# Digital_Processing.net
KiCad netlist of a schematic drawn in Altium Designer
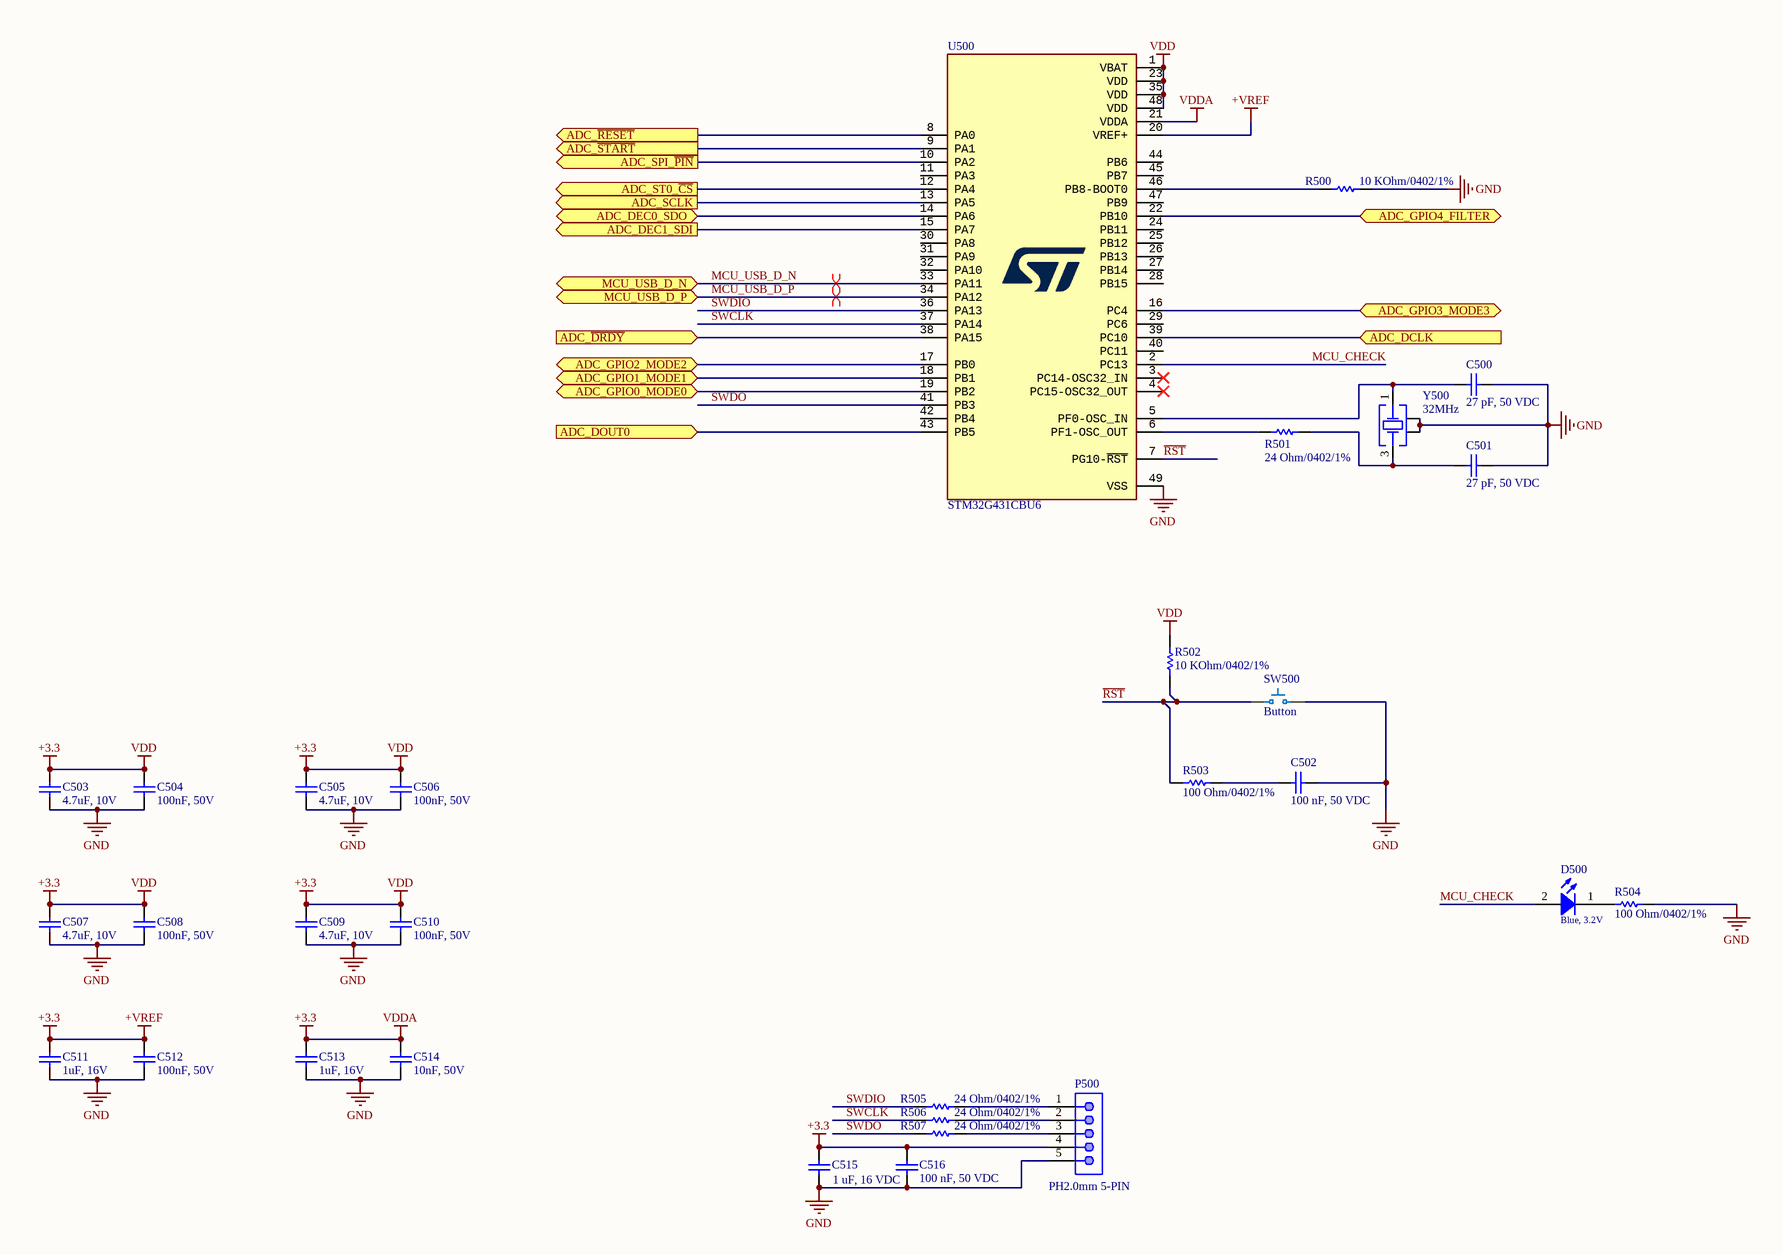
[diagram p0: Digital Processing.SchDoc]

(export (version "E")
  (design (tool "Eeschema 10.0.6"))
  (components
    (comp (ref "C500")
      (value "27 pF, 50 VDC")
      (footprint "CAP_0603")
      (description "CAP, size 0603, 22 pF, 50 VDC")
      (fields (field (name "TOLERANCE") "+/-5%"))
      (libsource (lib "Altium_Ceramic_Cap") (part "0106032200550"))
    )
    (comp (ref "C501")
      (value "27 pF, 50 VDC")
      (footprint "CAP_0603")
      (description "CAP, size 0603, 22 pF, 50 VDC")
      (fields (field (name "TOLERANCE") "+/-5%"))
      (libsource (lib "Altium_Ceramic_Cap") (part "0106032200550"))
    )
    (comp (ref "C502")
      (value "100 nF, 50 VDC")
      (footprint "CAP_0603")
      (description "CAP, size 0603, 100 nF, 50 VDC")
      (fields (field (name "TOLERANCE") "+/-10%"))
      (libsource (lib "Altium_Ceramic_Cap") (part "0106031041050"))
    )
    (comp (ref "C503")
      (value "4.7uF, 10V")
      (footprint "WCAP-CSGP_0402_L1W0.5H0.5")
      (description "WCAP-CSGP Multilayer Ceramic Chip Capacitor, General Purpose, size 0402, X5R, 4.7μF, 6.3V")
      (fields
        (field (name "MANUFACTURER PART NUMBER") "885012105008")
        (field (name "MANUFACTURER") "Wurth Elektronik")
      )
      (libsource (lib "Altium_WCAP-CSGP (rev24c)") (part "885012105008"))
    )
    (comp (ref "C504")
      (value "100nF, 50V")
      (footprint "WCAP-CSGP_0402_L1W0.5H0.5")
      (description "WCAP-CSGP Multilayer Ceramic Chip Capacitor, General Purpose, size 0402, X7R, 100nF, 50V")
      (fields
        (field (name "MANUFACTURER PART NUMBER") "885012205086")
        (field (name "MANUFACTURER") "Wurth Elektronik")
      )
      (libsource (lib "Altium_WCAP-CSGP (rev24c)") (part "885012205086"))
    )
    (comp (ref "C505")
      (value "4.7uF, 10V")
      (footprint "WCAP-CSGP_0402_L1W0.5H0.5")
      (description "WCAP-CSGP Multilayer Ceramic Chip Capacitor, General Purpose, size 0402, X5R, 4.7μF, 6.3V")
      (fields
        (field (name "MANUFACTURER PART NUMBER") "885012105008")
        (field (name "MANUFACTURER") "Wurth Elektronik")
      )
      (libsource (lib "Altium_WCAP-CSGP (rev24c)") (part "885012105008"))
    )
    (comp (ref "C506")
      (value "100nF, 50V")
      (footprint "WCAP-CSGP_0402_L1W0.5H0.5")
      (description "WCAP-CSGP Multilayer Ceramic Chip Capacitor, General Purpose, size 0402, X7R, 100nF, 50V")
      (fields
        (field (name "MANUFACTURER PART NUMBER") "885012205086")
        (field (name "MANUFACTURER") "Wurth Elektronik")
      )
      (libsource (lib "Altium_WCAP-CSGP (rev24c)") (part "885012205086"))
    )
    (comp (ref "C507")
      (value "4.7uF, 10V")
      (footprint "WCAP-CSGP_0402_L1W0.5H0.5")
      (description "WCAP-CSGP Multilayer Ceramic Chip Capacitor, General Purpose, size 0402, X5R, 4.7μF, 6.3V")
      (fields
        (field (name "MANUFACTURER PART NUMBER") "885012105008")
        (field (name "MANUFACTURER") "Wurth Elektronik")
      )
      (libsource (lib "Altium_WCAP-CSGP (rev24c)") (part "885012105008"))
    )
    (comp (ref "C508")
      (value "100nF, 50V")
      (footprint "WCAP-CSGP_0402_L1W0.5H0.5")
      (description "WCAP-CSGP Multilayer Ceramic Chip Capacitor, General Purpose, size 0402, X7R, 100nF, 50V")
      (fields
        (field (name "MANUFACTURER PART NUMBER") "885012205086")
        (field (name "MANUFACTURER") "Wurth Elektronik")
      )
      (libsource (lib "Altium_WCAP-CSGP (rev24c)") (part "885012205086"))
    )
    (comp (ref "C509")
      (value "4.7uF, 10V")
      (footprint "WCAP-CSGP_0402_L1W0.5H0.5")
      (description "WCAP-CSGP Multilayer Ceramic Chip Capacitor, General Purpose, size 0402, X5R, 4.7μF, 6.3V")
      (fields
        (field (name "MANUFACTURER PART NUMBER") "885012105008")
        (field (name "MANUFACTURER") "Wurth Elektronik")
      )
      (libsource (lib "Altium_WCAP-CSGP (rev24c)") (part "885012105008"))
    )
    (comp (ref "C510")
      (value "100nF, 50V")
      (footprint "WCAP-CSGP_0402_L1W0.5H0.5")
      (description "WCAP-CSGP Multilayer Ceramic Chip Capacitor, General Purpose, size 0402, X7R, 100nF, 50V")
      (fields
        (field (name "MANUFACTURER PART NUMBER") "885012205086")
        (field (name "MANUFACTURER") "Wurth Elektronik")
      )
      (libsource (lib "Altium_WCAP-CSGP (rev24c)") (part "885012205086"))
    )
    (comp (ref "C511")
      (value "1uF, 16V")
      (footprint "WCAP-CSGP_0402_L1W0.5H0.5")
      (description "1 µF ±10% 16V Ceramic Capacitor X7R 0603 (1608 Metric)")
      (fields
        (field (name "MANUFACTURER PART NUMBER") "885012105012")
        (field (name "MANUFACTURER") "Wurth Elektronik")
      )
      (libsource (lib "Altium_WCAP-CSGP (rev24c)") (part "885012105012"))
    )
    (comp (ref "C512")
      (value "100nF, 50V")
      (footprint "WCAP-CSGP_0402_L1W0.5H0.5")
      (description "WCAP-CSGP Multilayer Ceramic Chip Capacitor, General Purpose, size 0402, X7R, 100nF, 50V")
      (fields
        (field (name "MANUFACTURER PART NUMBER") "885012205086")
        (field (name "MANUFACTURER") "Wurth Elektronik")
      )
      (libsource (lib "Altium_WCAP-CSGP (rev24c)") (part "885012205086"))
    )
    (comp (ref "C513")
      (value "1uF, 16V")
      (footprint "WCAP-CSGP_0402_L1W0.5H0.5")
      (description "1 µF ±10% 16V Ceramic Capacitor X7R 0603 (1608 Metric)")
      (fields
        (field (name "MANUFACTURER PART NUMBER") "885012105012")
        (field (name "MANUFACTURER") "Wurth Elektronik")
      )
      (libsource (lib "Altium_WCAP-CSGP (rev24c)") (part "885012105012"))
    )
    (comp (ref "C514")
      (value "10nF, 50V")
      (footprint "WCAP-CSGP_0402_L1W0.5H0.5")
      (description "WCAP-CSGP Multilayer Ceramic Chip Capacitor, General Purpose, size 0402, X7R, 10nF, 50V")
      (fields
        (field (name "MANUFACTURER PART NUMBER") "885012205067")
        (field (name "MANUFACTURER") "Wurth Elektronik")
      )
      (libsource (lib "Altium_WCAP-CSGP (rev24c)") (part "885012205067"))
    )
    (comp (ref "C515")
      (value "1 uF, 16 VDC")
      (footprint "CAP_0603")
      (description "CAP, size 0603, 1 uF, 16 VDC")
      (fields (field (name "TOLERANCE") "+/-10%"))
      (libsource (lib "Altium_Ceramic_Cap") (part "0106031051016"))
    )
    (comp (ref "C516")
      (value "100 nF, 50 VDC")
      (footprint "CAP_0603")
      (description "CAP, size 0603, 100 nF, 50 VDC")
      (fields (field (name "TOLERANCE") "+/-10%"))
      (libsource (lib "Altium_Ceramic_Cap") (part "0106031041050"))
    )
    (comp (ref "D500")
      (value "Blue, 3.2V")
      (footprint "WL-SMCW_0805")
      (description "WL-SMCW SMT Mono-color Chip LED Waterclear, size 0805, Blue, 3.2V, 140deg")
      (libsource (lib "Altium_LED") (part "160805BlueClear"))
    )
    (comp (ref "P500")
      (value "PH2.0mm 5-PIN")
      (footprint "620105131822")
      (description "WR-WTB SMT Male Horizontal Shrouded Header, pitch 2mm, 5p")
      (fields (field (name "PART NUMBER") "620105131822") (field (name "MANUFACTURER") "Wurth Elektronik"))
      (libsource (lib "Altium_PCB_Connector") (part "620105131822"))
    )
    (comp (ref "R500")
      (value "10 KOhm/0402/1%")
      (footprint "R0402")
      (description "Code 103, 1/16W 1%")
      (fields (field (name "Comment") "Resistor 10 KOhm 0402 1%"))
      (libsource (lib "Giang_Resistor") (part "Resistor 10 KOhm 0402 1%"))
    )
    (comp (ref "R501")
      (value "24 Ohm/0402/1%")
      (footprint "R0402")
      (description "1/16W Thick Film Resistors 50V ±5% ±200ppm/℃ 24Ω 0402 Chip Resistor - Surface Mount ROHS")
      (fields (field (name "Comment") "Resistor 24 Ohm 0402 1%"))
      (libsource (lib "Giang_Resistor") (part "Resistor 24 Ohm 0402 1%"))
    )
    (comp (ref "R502")
      (value "10 KOhm/0402/1%")
      (footprint "R0402")
      (description "Code 103, 1/16W 1%")
      (fields (field (name "Comment") "Resistor 10 KOhm 0402 1%"))
      (libsource (lib "Giang_Resistor") (part "Resistor 10 KOhm 0402 1%"))
    )
    (comp (ref "R503")
      (value "100 Ohm/0402/1%")
      (footprint "R0402")
      (description "Code 104, 1/16W")
      (fields (field (name "Comment") "Resistor 100 Ohm 0402 1%"))
      (libsource (lib "Giang_Resistor") (part "Resistor 100 Ohm 0402 1%"))
    )
    (comp (ref "R504")
      (value "100 Ohm/0402/1%")
      (footprint "R0402")
      (description "Code 104, 1/16W")
      (fields (field (name "Comment") "Resistor 100 Ohm 0402 1%"))
      (libsource (lib "Giang_Resistor") (part "Resistor 100 Ohm 0402 1%"))
    )
    (comp (ref "R505")
      (value "24 Ohm/0402/1%")
      (footprint "R0402")
      (description "1/16W Thick Film Resistors 50V ±5% ±200ppm/℃ 24Ω 0402 Chip Resistor - Surface Mount ROHS")
      (fields (field (name "Comment") "Resistor 24 Ohm 0402 1%"))
      (libsource (lib "Giang_Resistor") (part "Resistor 24 Ohm 0402 1%"))
    )
    (comp (ref "R506")
      (value "24 Ohm/0402/1%")
      (footprint "R0402")
      (description "1/16W Thick Film Resistors 50V ±5% ±200ppm/℃ 24Ω 0402 Chip Resistor - Surface Mount ROHS")
      (fields (field (name "Comment") "Resistor 24 Ohm 0402 1%"))
      (libsource (lib "Giang_Resistor") (part "Resistor 24 Ohm 0402 1%"))
    )
    (comp (ref "R507")
      (value "24 Ohm/0402/1%")
      (footprint "R0402")
      (description "1/16W Thick Film Resistors 50V ±5% ±200ppm/℃ 24Ω 0402 Chip Resistor - Surface Mount ROHS")
      (fields (field (name "Comment") "Resistor 24 Ohm 0402 1%"))
      (libsource (lib "Giang_Resistor") (part "Resistor 24 Ohm 0402 1%"))
    )
    (comp (ref "SW500")
      (value "Button")
      (footprint "Button_3x4mm_SMD_2P")
      (fields (field (name "SUPPLY PART NUMBER") "Tụ Gốm 0603 20pF 50V"))
      (libsource (lib "BluetoothTracking") (part "Button_SMD_3x4mm_2P"))
    )
    (comp (ref "U500")
      (value "STM32G431CBU6")
      (footprint "QFN50P700X700X60-49N")
      (libsource (lib "Giang_MCU") (part "STM32G431CBU6"))
    )
    (comp (ref "Y500")
      (value "32MHz")
      (footprint "WE-XTAL_CFPX-104")
      (description "WE-XTAL Quartz Crystal, SMT, CFPX-104, 32MHz, +/-20ppm")
      (fields
        (field (name "MANUFACTURER PART NUMBER") "830059535")
        (field (name "MANUFACTURER") "Wurth Elektronik")
      )
      (libsource (lib "Altium_WE-XTAL (rev22a)") (part "830059535"))
    )
  )
  (nets
    (net (code "1") (name "+3.3") (class "Default")
      (node (ref "C503") (pin "2") (pinfunction "2_2") (pintype "passive"))
      (node (ref "C504") (pin "2") (pinfunction "2_2") (pintype "passive"))
      (node (ref "C505") (pin "2") (pinfunction "2_2") (pintype "passive"))
      (node (ref "C506") (pin "2") (pinfunction "2_2") (pintype "passive"))
      (node (ref "C507") (pin "2") (pinfunction "2_2") (pintype "passive"))
      (node (ref "C508") (pin "2") (pinfunction "2_2") (pintype "passive"))
      (node (ref "C509") (pin "2") (pinfunction "2_2") (pintype "passive"))
      (node (ref "C510") (pin "2") (pinfunction "2_2") (pintype "passive"))
      (node (ref "C511") (pin "1") (pinfunction "1_1") (pintype "passive"))
      (node (ref "C512") (pin "2") (pinfunction "2_2") (pintype "passive"))
      (node (ref "C513") (pin "1") (pinfunction "1_1") (pintype "passive"))
      (node (ref "C514") (pin "2") (pinfunction "2_2") (pintype "passive"))
      (node (ref "C515") (pin "2") (pinfunction "2_2") (pintype "passive"))
      (node (ref "C516") (pin "1") (pinfunction "1_1") (pintype "passive"))
      (node (ref "P500") (pin "4") (pinfunction "4_4") (pintype "passive"))
      (node (ref "R502") (pin "1") (pinfunction "1_1") (pintype "passive"))
      (node (ref "U500") (pin "1") (pinfunction "VBAT_1") (pintype "passive"))
      (node (ref "U500") (pin "20") (pinfunction "VREF+_20") (pintype "passive"))
      (node (ref "U500") (pin "21") (pinfunction "VDDA_21") (pintype "passive"))
      (node (ref "U500") (pin "23") (pinfunction "VDD_23") (pintype "passive"))
      (node (ref "U500") (pin "35") (pinfunction "VDD_35") (pintype "passive"))
      (node (ref "U500") (pin "48") (pinfunction "VDD_48") (pintype "passive"))
    )
    (net (code "2") (name "/ADC_DCLK") (class "Default")
      (node (ref "U500") (pin "39") (pinfunction "PC10_39") (pintype "passive"))
    )
    (net (code "3") (name "/ADC_DEC0_SDO") (class "Default")
      (node (ref "U500") (pin "14") (pinfunction "PA6_14") (pintype "passive"))
    )
    (net (code "4") (name "/ADC_DEC1_SDI") (class "Default")
      (node (ref "U500") (pin "15") (pinfunction "PA7_15") (pintype "passive"))
    )
    (net (code "5") (name "/ADC_DOUT0") (class "Default")
      (node (ref "U500") (pin "43") (pinfunction "PB5_43") (pintype "passive"))
    )
    (net (code "6") (name "/ADC_GPIO0_MODE0") (class "Default")
      (node (ref "U500") (pin "19") (pinfunction "PB2_19") (pintype "passive"))
    )
    (net (code "7") (name "/ADC_GPIO1_MODE1") (class "Default")
      (node (ref "U500") (pin "18") (pinfunction "PB1_18") (pintype "passive"))
    )
    (net (code "8") (name "/ADC_GPIO2_MODE2") (class "Default")
      (node (ref "U500") (pin "17") (pinfunction "PB0_17") (pintype "passive"))
    )
    (net (code "9") (name "/ADC_GPIO3_MODE3") (class "Default")
      (node (ref "U500") (pin "16") (pinfunction "PC4_16") (pintype "passive"))
    )
    (net (code "10") (name "/ADC_GPIO4_FILTER") (class "Default")
      (node (ref "U500") (pin "22") (pinfunction "PB10_22") (pintype "passive"))
    )
    (net (code "11") (name "/ADC_SCLK") (class "Default")
      (node (ref "U500") (pin "13") (pinfunction "PA5_13") (pintype "passive"))
    )
    (net (code "12") (name "/ADC_SPI_~{PIN}") (class "Default")
      (node (ref "U500") (pin "10") (pinfunction "PA2_10") (pintype "passive"))
    )
    (net (code "13") (name "/ADC_ST0_~{CS}") (class "Default")
      (node (ref "U500") (pin "12") (pinfunction "PA4_12") (pintype "passive"))
    )
    (net (code "14") (name "/ADC_~{DRDY}") (class "Default")
      (node (ref "U500") (pin "38") (pinfunction "PA15_38") (pintype "passive"))
    )
    (net (code "15") (name "/ADC_~{RESET}") (class "Default")
      (node (ref "U500") (pin "8") (pinfunction "PA0_8") (pintype "passive"))
    )
    (net (code "16") (name "/ADC_~{START}") (class "Default")
      (node (ref "U500") (pin "9") (pinfunction "PA1_9") (pintype "passive"))
    )
    (net (code "17") (name "/MCU_CHECK") (class "Default")
      (node (ref "D500") (pin "2") (pinfunction "A_2") (pintype "passive"))
      (node (ref "U500") (pin "2") (pinfunction "PC13_2") (pintype "passive"))
    )
    (net (code "18") (name "/MCU_USB_D_N") (class "Default")
      (node (ref "U500") (pin "33") (pinfunction "PA11_33") (pintype "passive"))
    )
    (net (code "19") (name "/MCU_USB_D_P") (class "Default")
      (node (ref "U500") (pin "34") (pinfunction "PA12_34") (pintype "passive"))
    )
    (net (code "20") (name "/SWCLK") (class "Default")
      (node (ref "R506") (pin "1") (pinfunction "1_1") (pintype "passive"))
      (node (ref "U500") (pin "37") (pinfunction "PA14_37") (pintype "passive"))
    )
    (net (code "21") (name "/SWDIO") (class "Default")
      (node (ref "R505") (pin "1") (pinfunction "1_1") (pintype "passive"))
      (node (ref "U500") (pin "36") (pinfunction "PA13_36") (pintype "passive"))
    )
    (net (code "22") (name "/SWDO") (class "Default")
      (node (ref "R507") (pin "1") (pinfunction "1_1") (pintype "passive"))
      (node (ref "U500") (pin "41") (pinfunction "PB3_41") (pintype "passive"))
    )
    (net (code "23") (name "/~{RST}") (class "Default")
      (node (ref "R502") (pin "2") (pinfunction "2_2") (pintype "passive"))
      (node (ref "R503") (pin "1") (pinfunction "1_1") (pintype "passive"))
      (node (ref "SW500") (pin "1") (pinfunction "1_1") (pintype "passive"))
      (node (ref "U500") (pin "7") (pinfunction "PG10-~{RST}_7") (pintype "passive"))
    )
    (net (code "24") (name "GND") (class "Default")
      (node (ref "C500") (pin "1") (pinfunction "1_1") (pintype "passive"))
      (node (ref "C501") (pin "1") (pinfunction "1_1") (pintype "passive"))
      (node (ref "C502") (pin "2") (pinfunction "2_2") (pintype "passive"))
      (node (ref "C503") (pin "1") (pinfunction "1_1") (pintype "passive"))
      (node (ref "C504") (pin "1") (pinfunction "1_1") (pintype "passive"))
      (node (ref "C505") (pin "1") (pinfunction "1_1") (pintype "passive"))
      (node (ref "C506") (pin "1") (pinfunction "1_1") (pintype "passive"))
      (node (ref "C507") (pin "1") (pinfunction "1_1") (pintype "passive"))
      (node (ref "C508") (pin "1") (pinfunction "1_1") (pintype "passive"))
      (node (ref "C509") (pin "1") (pinfunction "1_1") (pintype "passive"))
      (node (ref "C510") (pin "1") (pinfunction "1_1") (pintype "passive"))
      (node (ref "C511") (pin "2") (pinfunction "2_2") (pintype "passive"))
      (node (ref "C512") (pin "1") (pinfunction "1_1") (pintype "passive"))
      (node (ref "C513") (pin "2") (pinfunction "2_2") (pintype "passive"))
      (node (ref "C514") (pin "1") (pinfunction "1_1") (pintype "passive"))
      (node (ref "C515") (pin "1") (pinfunction "1_1") (pintype "passive"))
      (node (ref "C516") (pin "2") (pinfunction "2_2") (pintype "passive"))
      (node (ref "P500") (pin "5") (pinfunction "5_5") (pintype "passive"))
      (node (ref "R500") (pin "2") (pinfunction "2_2") (pintype "passive"))
      (node (ref "R504") (pin "2") (pinfunction "2_2") (pintype "passive"))
      (node (ref "SW500") (pin "2") (pinfunction "2_2") (pintype "passive"))
      (node (ref "U500") (pin "49") (pinfunction "VSS_49") (pintype "passive"))
      (node (ref "Y500") (pin "2") (pinfunction "GND_&_Lid_2") (pintype "passive"))
      (node (ref "Y500") (pin "4") (pinfunction "GND_&_Lid_4") (pintype "passive"))
    )
    (net (code "25") (name "Net-(C501-Pad2)") (class "Default")
      (node (ref "C501") (pin "2") (pinfunction "2_2") (pintype "passive"))
      (node (ref "R501") (pin "2") (pinfunction "2_2") (pintype "passive"))
      (node (ref "Y500") (pin "3") (pinfunction "Crystal_3") (pintype "passive"))
    )
    (net (code "26") (name "Net-(C502-Pad1)") (class "Default")
      (node (ref "C502") (pin "1") (pinfunction "1_1") (pintype "passive"))
      (node (ref "R503") (pin "2") (pinfunction "2_2") (pintype "passive"))
    )
    (net (code "27") (name "Net-(D500-K)") (class "Default")
      (node (ref "D500") (pin "1") (pinfunction "K_1") (pintype "passive"))
      (node (ref "R504") (pin "1") (pinfunction "1_1") (pintype "passive"))
    )
    (net (code "28") (name "Net-(P500-Pad1)") (class "Default")
      (node (ref "P500") (pin "1") (pinfunction "1_1") (pintype "passive"))
      (node (ref "R505") (pin "2") (pinfunction "2_2") (pintype "passive"))
    )
    (net (code "29") (name "Net-(P500-Pad2)") (class "Default")
      (node (ref "P500") (pin "2") (pinfunction "2_2") (pintype "passive"))
      (node (ref "R506") (pin "2") (pinfunction "2_2") (pintype "passive"))
    )
    (net (code "30") (name "Net-(P500-Pad3)") (class "Default")
      (node (ref "P500") (pin "3") (pinfunction "3_3") (pintype "passive"))
      (node (ref "R507") (pin "2") (pinfunction "2_2") (pintype "passive"))
    )
    (net (code "31") (name "Net-(U500-PB8-BOOT0)") (class "Default")
      (node (ref "R500") (pin "1") (pinfunction "1_1") (pintype "passive"))
      (node (ref "U500") (pin "46") (pinfunction "PB8-BOOT0_46") (pintype "passive"))
    )
    (net (code "32") (name "Net-(U500-PF0-OSC_IN)") (class "Default")
      (node (ref "C500") (pin "2") (pinfunction "2_2") (pintype "passive"))
      (node (ref "U500") (pin "5") (pinfunction "PF0-OSC_IN_5") (pintype "passive"))
      (node (ref "Y500") (pin "1") (pinfunction "Crystal_1") (pintype "passive"))
    )
    (net (code "33") (name "Net-(U500-PF1-OSC_OUT)") (class "Default")
      (node (ref "R501") (pin "1") (pinfunction "1_1") (pintype "passive"))
      (node (ref "U500") (pin "6") (pinfunction "PF1-OSC_OUT_6") (pintype "passive"))
    )
    (net (code "34") (name "unconnected-(U500-PA3-Pad11)") (class "Default")
      (node (ref "U500") (pin "11") (pinfunction "PA3_11") (pintype "passive"))
    )
    (net (code "35") (name "unconnected-(U500-PA8-Pad30)") (class "Default")
      (node (ref "U500") (pin "30") (pinfunction "PA8_30") (pintype "passive"))
    )
    (net (code "36") (name "unconnected-(U500-PA9-Pad31)") (class "Default")
      (node (ref "U500") (pin "31") (pinfunction "PA9_31") (pintype "passive"))
    )
    (net (code "37") (name "unconnected-(U500-PA10-Pad32)") (class "Default")
      (node (ref "U500") (pin "32") (pinfunction "PA10_32") (pintype "passive"))
    )
    (net (code "38") (name "unconnected-(U500-PB4-Pad42)") (class "Default")
      (node (ref "U500") (pin "42") (pinfunction "PB4_42") (pintype "passive"))
    )
    (net (code "39") (name "unconnected-(U500-PB6-Pad44)") (class "Default")
      (node (ref "U500") (pin "44") (pinfunction "PB6_44") (pintype "passive"))
    )
    (net (code "40") (name "unconnected-(U500-PB7-Pad45)") (class "Default")
      (node (ref "U500") (pin "45") (pinfunction "PB7_45") (pintype "passive"))
    )
    (net (code "41") (name "unconnected-(U500-PB9-Pad47)") (class "Default")
      (node (ref "U500") (pin "47") (pinfunction "PB9_47") (pintype "passive"))
    )
    (net (code "42") (name "unconnected-(U500-PB11-Pad24)") (class "Default")
      (node (ref "U500") (pin "24") (pinfunction "PB11_24") (pintype "passive"))
    )
    (net (code "43") (name "unconnected-(U500-PB12-Pad25)") (class "Default")
      (node (ref "U500") (pin "25") (pinfunction "PB12_25") (pintype "passive"))
    )
    (net (code "44") (name "unconnected-(U500-PB13-Pad26)") (class "Default")
      (node (ref "U500") (pin "26") (pinfunction "PB13_26") (pintype "passive"))
    )
    (net (code "45") (name "unconnected-(U500-PB14-Pad27)") (class "Default")
      (node (ref "U500") (pin "27") (pinfunction "PB14_27") (pintype "passive"))
    )
    (net (code "46") (name "unconnected-(U500-PB15-Pad28)") (class "Default")
      (node (ref "U500") (pin "28") (pinfunction "PB15_28") (pintype "passive"))
    )
    (net (code "47") (name "unconnected-(U500-PC6-Pad29)") (class "Default")
      (node (ref "U500") (pin "29") (pinfunction "PC6_29") (pintype "passive"))
    )
    (net (code "48") (name "unconnected-(U500-PC11-Pad40)") (class "Default")
      (node (ref "U500") (pin "40") (pinfunction "PC11_40") (pintype "passive"))
    )
    (net (code "49") (name "unconnected-(U500-PC14-OSC32_IN-Pad3)") (class "Default")
      (node (ref "U500") (pin "3") (pinfunction "PC14-OSC32_IN_3") (pintype "passive+no_connect"))
    )
    (net (code "50") (name "unconnected-(U500-PC15-OSC32_OUT-Pad4)") (class "Default")
      (node (ref "U500") (pin "4") (pinfunction "PC15-OSC32_OUT_4") (pintype "passive+no_connect"))
    )
  )
)
